# nrf_ha_sensor_Particles.net
KiCad netlist of a schematic drawn in Altium Designer
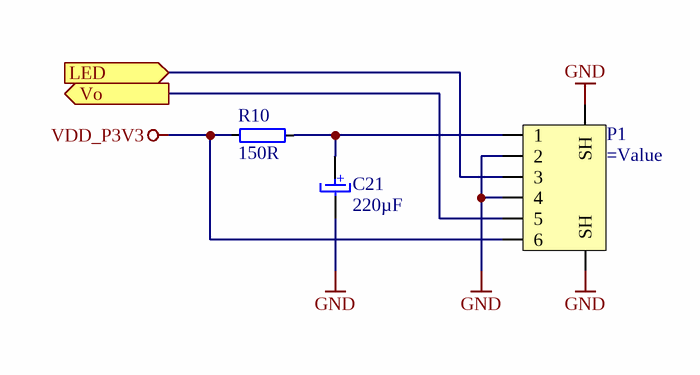
[diagram p0: nrf_ha_sensor_Particles.SchDoc]

(export (version "E")
  (design (tool "Eeschema 10.0.6"))
  (components
    (comp (ref "C21")
      (value "220µF")
      (footprint "CAPPR200-500X1100")
      (description "Capacitor, Radial Aluminum Electrolytic, ±20%")
      (fields
        (field (name "PART NUMBER") "Cap-Electrolyt-47µF/25V")
        (field (name "MANUFACTURER") "Multicomp")
        (field (name "PUBLISHER") "Nordic Semiconductor")
      )
      (libsource (lib "Nordic Passive DB") (part "CAP_pol"))
    )
    (comp (ref "P1")
      (value "~")
      (footprint "S6B-ZR-SM4A-TF")
      (libsource (lib "S6B-ZR-SM4A-TF") (part "S6B-ZR-SM4A-TF"))
    )
    (comp (ref "R10")
      (value "150R")
      (footprint "RESC1005X04L")
      (description "Resistor, ±1%, 0.063W")
      (fields (field (name "PART NUMBER") "R0402-150") (field (name "PUBLISHER") "Nordic Semiconductor"))
      (libsource (lib "Nordic Passive DB") (part "RES"))
    )
  )
  (nets
    (net (code "1") (name "/LED") (class "Default")
      (node (ref "P1") (pin "3") (pinfunction "3_3") (pintype "passive"))
    )
    (net (code "2") (name "/Vo") (class "Default")
      (node (ref "P1") (pin "5") (pinfunction "5_5") (pintype "passive"))
    )
    (net (code "3") (name "GND") (class "Default")
      (node (ref "C21") (pin "1") (pinfunction "NEG_1") (pintype "passive"))
      (node (ref "P1") (pin "2") (pinfunction "2_2") (pintype "passive"))
      (node (ref "P1") (pin "4") (pinfunction "4_4") (pintype "passive"))
      (node (ref "P1") (pin "SH1") (pinfunction "SH_SH1") (pintype "passive"))
      (node (ref "P1") (pin "SH2") (pinfunction "SH_SH2") (pintype "passive"))
    )
    (net (code "4") (name "Net-(C21-POS)") (class "Default")
      (node (ref "C21") (pin "2") (pinfunction "POS_2") (pintype "passive"))
      (node (ref "P1") (pin "1") (pinfunction "1_1") (pintype "passive"))
      (node (ref "R10") (pin "2") (pinfunction "2_2") (pintype "passive"))
    )
    (net (code "5") (name "VDD_P3V3") (class "Default")
      (node (ref "P1") (pin "6") (pinfunction "6_6") (pintype "passive"))
      (node (ref "R10") (pin "1") (pinfunction "1_1") (pintype "passive"))
    )
  )
)
